# 2014_CanSat_main.net
KiCad netlist of a schematic drawn in EAGLE
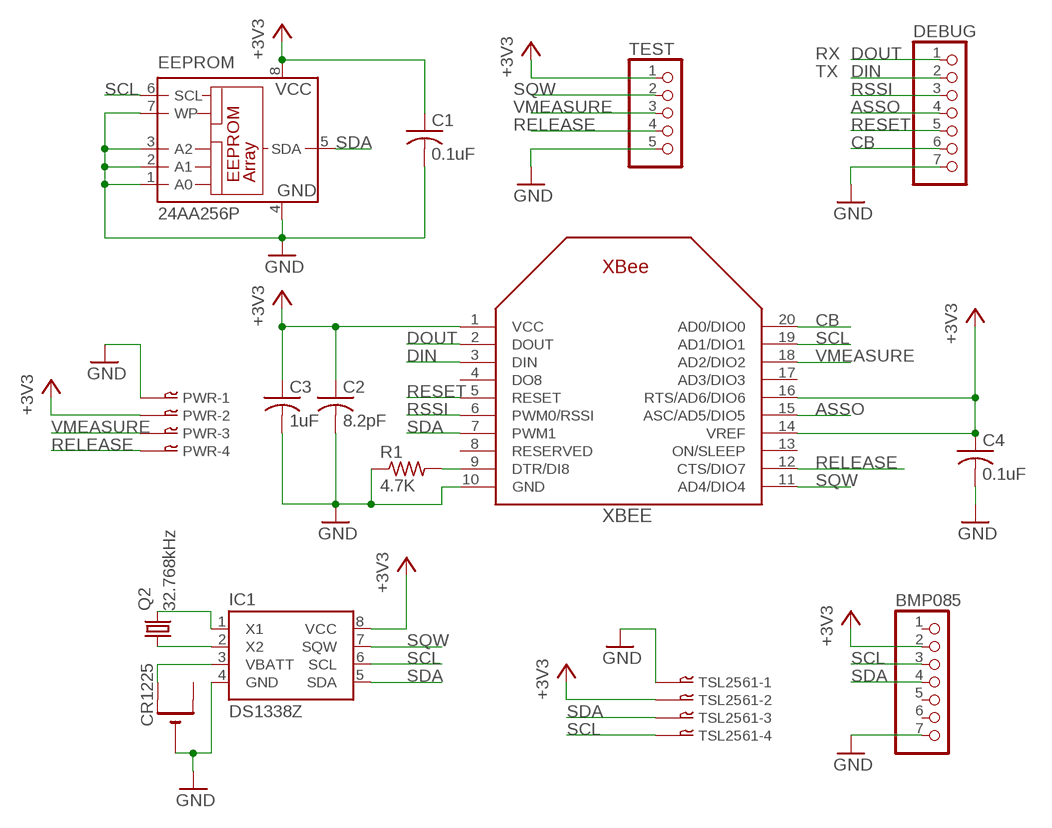
[diagram p0: schematic, sheet 1]

(export (version "E")
  (design (tool "Eeschema 10.0.6"))
  (components
    (comp (ref "BMP085")
      (value "PINHD-1X7")
      (footprint "eagle-import:1X07")
      (libsource (lib "eagle-import") (part "PINHD-1X7"))
    )
    (comp (ref "C1")
      (value "0.1uF")
      (footprint "eagle-import:C050-024X044")
      (libsource (lib "eagle-import") (part "C-US050-024X044"))
    )
    (comp (ref "C2")
      (value "8.2pF")
      (footprint "eagle-import:C050-024X044")
      (libsource (lib "eagle-import") (part "C-US050-024X044"))
    )
    (comp (ref "C3")
      (value "1uF")
      (footprint "eagle-import:C050-024X044")
      (libsource (lib "eagle-import") (part "C-US050-024X044"))
    )
    (comp (ref "C4")
      (value "0.1uF")
      (footprint "eagle-import:C050-024X044")
      (libsource (lib "eagle-import") (part "C-US050-024X044"))
    )
    (comp (ref "CR1225")
      (value "CR1220THM")
      (footprint "eagle-import:CR1220-THM")
      (libsource (lib "eagle-import") (part "CR1220THM"))
    )
    (comp (ref "DEBUG")
      (value "PINHD-1X7")
      (footprint "eagle-import:1X07")
      (libsource (lib "eagle-import") (part "PINHD-1X7"))
    )
    (comp (ref "EEPROM")
      (value "24AA256P")
      (footprint "eagle-import:DIL8")
      (fields (field (name "MF") "MICROCHIP") (field (name "MPN") "24AA256-I/P"))
      (libsource (lib "eagle-import") (part "24PAA256"))
    )
    (comp (ref "IC1")
      (value "DS1338Z")
      (footprint "eagle-import:SO08")
      (libsource (lib "eagle-import") (part "DS1338Z"))
    )
    (comp (ref "PWR")
      (value "04-JST-B4B-XH-A")
      (footprint "eagle-import:B4B-XH")
      (libsource (lib "eagle-import") (part "04-JST-B4B-XH-A"))
    )
    (comp (ref "Q2")
      (value "32.768kHz")
      (footprint "eagle-import:TC26H")
      (libsource (lib "eagle-import") (part "CRYSTALTC26H"))
    )
    (comp (ref "R1")
      (value "4.7K")
      (footprint "eagle-import:0309_10")
      (libsource (lib "eagle-import") (part "R-US_0309/10"))
    )
    (comp (ref "TEST")
      (value "PINHD-1X5")
      (footprint "eagle-import:1X05")
      (libsource (lib "eagle-import") (part "PINHD-1X5"))
    )
    (comp (ref "TSL2561")
      (value "04-JST-B4B-XH-A")
      (footprint "eagle-import:B4B-XH")
      (libsource (lib "eagle-import") (part "04-JST-B4B-XH-A"))
    )
    (comp (ref "XBEE")
      (value "XBEE")
      (footprint "eagle-import:XBEE")
      (libsource (lib "eagle-import") (part "XBEE"))
    )
  )
  (nets
    (net (code "1") (name "+3V3") (class "Default")
      (node (ref "BMP085") (pin "2") (pinfunction "2_2") (pintype "passive"))
      (node (ref "C1") (pin "1") (pinfunction "1_1") (pintype "passive"))
      (node (ref "C2") (pin "1") (pinfunction "1_1") (pintype "passive"))
      (node (ref "C3") (pin "1") (pinfunction "1_1") (pintype "passive"))
      (node (ref "C4") (pin "1") (pinfunction "1_1") (pintype "passive"))
      (node (ref "EEPROM") (pin "8") (pinfunction "VCC_8") (pintype "power_in"))
      (node (ref "IC1") (pin "8") (pinfunction "VCC_8") (pintype "bidirectional"))
      (node (ref "PWR") (pin "P$2") (pinfunction "1_P$2") (pintype "passive"))
      (node (ref "TEST") (pin "1") (pinfunction "1_1") (pintype "passive"))
      (node (ref "TSL2561") (pin "P$2") (pinfunction "1_P$2") (pintype "passive"))
      (node (ref "XBEE") (pin "1") (pinfunction "VCC_1") (pintype "power_in"))
      (node (ref "XBEE") (pin "14") (pinfunction "VREF_14") (pintype "input"))
      (node (ref "XBEE") (pin "16") (pinfunction "RTS/AD6/DIO6_16") (pintype "bidirectional"))
    )
    (net (code "2") (name "/ASSO") (class "Default")
      (node (ref "DEBUG") (pin "4") (pinfunction "4_4") (pintype "passive"))
      (node (ref "XBEE") (pin "15") (pinfunction "ASC/AD5/DIO5_15") (pintype "bidirectional"))
    )
    (net (code "3") (name "/CB") (class "Default")
      (node (ref "DEBUG") (pin "6") (pinfunction "6_6") (pintype "passive"))
      (node (ref "XBEE") (pin "20") (pinfunction "AD0/DIO0_20") (pintype "bidirectional"))
    )
    (net (code "4") (name "/DIN") (class "Default")
      (node (ref "DEBUG") (pin "2") (pinfunction "2_2") (pintype "passive"))
      (node (ref "XBEE") (pin "3") (pinfunction "DIN_3") (pintype "input"))
    )
    (net (code "5") (name "/DOUT") (class "Default")
      (node (ref "DEBUG") (pin "1") (pinfunction "1_1") (pintype "passive"))
      (node (ref "XBEE") (pin "2") (pinfunction "DOUT_2") (pintype "output"))
    )
    (net (code "6") (name "/RELEASE") (class "Default")
      (node (ref "PWR") (pin "P$4") (pinfunction "1_P$4") (pintype "passive"))
      (node (ref "TEST") (pin "4") (pinfunction "4_4") (pintype "passive"))
      (node (ref "XBEE") (pin "12") (pinfunction "CTS/DIO7_12") (pintype "bidirectional"))
    )
    (net (code "7") (name "/RESET") (class "Default")
      (node (ref "DEBUG") (pin "5") (pinfunction "5_5") (pintype "passive"))
      (node (ref "XBEE") (pin "5") (pinfunction "RESET_5") (pintype "input"))
    )
    (net (code "8") (name "/RSSI") (class "Default")
      (node (ref "DEBUG") (pin "3") (pinfunction "3_3") (pintype "passive"))
      (node (ref "XBEE") (pin "6") (pinfunction "PWM0/RSSI_6") (pintype "output"))
    )
    (net (code "9") (name "/SCL") (class "Default")
      (node (ref "BMP085") (pin "3") (pinfunction "3_3") (pintype "passive"))
      (node (ref "EEPROM") (pin "6") (pinfunction "SCL_6") (pintype "input"))
      (node (ref "IC1") (pin "6") (pinfunction "SCL_6") (pintype "bidirectional"))
      (node (ref "TSL2561") (pin "P$4") (pinfunction "1_P$4") (pintype "passive"))
      (node (ref "XBEE") (pin "19") (pinfunction "AD1/DIO1_19") (pintype "bidirectional"))
    )
    (net (code "10") (name "/SDA") (class "Default")
      (node (ref "BMP085") (pin "4") (pinfunction "4_4") (pintype "passive"))
      (node (ref "EEPROM") (pin "5") (pinfunction "SDA_5") (pintype "bidirectional"))
      (node (ref "IC1") (pin "5") (pinfunction "SDA_5") (pintype "bidirectional"))
      (node (ref "TSL2561") (pin "P$3") (pinfunction "1_P$3") (pintype "passive"))
      (node (ref "XBEE") (pin "7") (pinfunction "PWM1_7") (pintype "output"))
    )
    (net (code "11") (name "/SQW") (class "Default")
      (node (ref "IC1") (pin "7") (pinfunction "SQW_7") (pintype "bidirectional"))
      (node (ref "TEST") (pin "2") (pinfunction "2_2") (pintype "passive"))
      (node (ref "XBEE") (pin "11") (pinfunction "AD4/DIO4_11") (pintype "bidirectional"))
    )
    (net (code "12") (name "/VMEASURE") (class "Default")
      (node (ref "PWR") (pin "P$3") (pinfunction "1_P$3") (pintype "passive"))
      (node (ref "TEST") (pin "3") (pinfunction "3_3") (pintype "passive"))
      (node (ref "XBEE") (pin "18") (pinfunction "AD2/DIO2_18") (pintype "bidirectional"))
    )
    (net (code "13") (name "GND") (class "Default")
      (node (ref "BMP085") (pin "7") (pinfunction "7_7") (pintype "passive"))
      (node (ref "C1") (pin "2") (pinfunction "2_2") (pintype "passive"))
      (node (ref "C2") (pin "2") (pinfunction "2_2") (pintype "passive"))
      (node (ref "C3") (pin "2") (pinfunction "2_2") (pintype "passive"))
      (node (ref "C4") (pin "2") (pinfunction "2_2") (pintype "passive"))
      (node (ref "CR1225") (pin "-") (pinfunction "-_-") (pintype "passive"))
      (node (ref "DEBUG") (pin "7") (pinfunction "7_7") (pintype "passive"))
      (node (ref "EEPROM") (pin "1") (pinfunction "A0_1") (pintype "input"))
      (node (ref "EEPROM") (pin "2") (pinfunction "A1_2") (pintype "input"))
      (node (ref "EEPROM") (pin "3") (pinfunction "A2_3") (pintype "input"))
      (node (ref "EEPROM") (pin "4") (pinfunction "GND_4") (pintype "power_in"))
      (node (ref "EEPROM") (pin "7") (pinfunction "WP_7") (pintype "input"))
      (node (ref "IC1") (pin "4") (pinfunction "GND_4") (pintype "bidirectional"))
      (node (ref "PWR") (pin "P$1") (pinfunction "1_P$1") (pintype "passive"))
      (node (ref "R1") (pin "1") (pinfunction "1_1") (pintype "passive"))
      (node (ref "TEST") (pin "5") (pinfunction "5_5") (pintype "passive"))
      (node (ref "TSL2561") (pin "P$1") (pinfunction "1_P$1") (pintype "passive"))
      (node (ref "XBEE") (pin "10") (pinfunction "GND_10") (pintype "power_in"))
    )
    (net (code "14") (name "Net-(CR1225-+)") (class "Default")
      (node (ref "CR1225") (pin "+1") (pinfunction "+_+1") (pintype "passive"))
      (node (ref "IC1") (pin "3") (pinfunction "VBATT_3") (pintype "bidirectional"))
    )
    (net (code "15") (name "Net-(IC1-X1)") (class "Default")
      (node (ref "IC1") (pin "1") (pinfunction "X1_1") (pintype "bidirectional"))
      (node (ref "Q2") (pin "2") (pinfunction "2_2") (pintype "passive"))
    )
    (net (code "16") (name "Net-(IC1-X2)") (class "Default")
      (node (ref "IC1") (pin "2") (pinfunction "X2_2") (pintype "bidirectional"))
      (node (ref "Q2") (pin "1") (pinfunction "1_1") (pintype "passive"))
    )
    (net (code "17") (name "Net-(XBEE-DTR{slash}DI8)") (class "Default")
      (node (ref "R1") (pin "2") (pinfunction "2_2") (pintype "passive"))
      (node (ref "XBEE") (pin "9") (pinfunction "DTR/DI8_9") (pintype "input"))
    )
    (net (code "18") (name "unconnected-(BMP085-Pad1)") (class "Default")
      (node (ref "BMP085") (pin "1") (pinfunction "1_1") (pintype "passive"))
    )
    (net (code "19") (name "unconnected-(BMP085-Pad5)") (class "Default")
      (node (ref "BMP085") (pin "5") (pinfunction "5_5") (pintype "passive"))
    )
    (net (code "20") (name "unconnected-(BMP085-Pad6)") (class "Default")
      (node (ref "BMP085") (pin "6") (pinfunction "6_6") (pintype "passive"))
    )
    (net (code "21") (name "unconnected-(CR1225-+1-Pad+2)") (class "Default")
      (node (ref "CR1225") (pin "+2") (pinfunction "+1_+2") (pintype "passive"))
    )
    (net (code "22") (name "unconnected-(XBEE-AD3{slash}DIO3-Pad17)") (class "Default")
      (node (ref "XBEE") (pin "17") (pinfunction "AD3/DIO3_17") (pintype "bidirectional"))
    )
    (net (code "23") (name "unconnected-(XBEE-DO8-Pad4)") (class "Default")
      (node (ref "XBEE") (pin "4") (pinfunction "DO8_4") (pintype "output"))
    )
    (net (code "24") (name "unconnected-(XBEE-ON{slash}SLEEP-Pad13)") (class "Default")
      (node (ref "XBEE") (pin "13") (pinfunction "ON/SLEEP_13") (pintype "output"))
    )
    (net (code "25") (name "unconnected-(XBEE-RESERVED-Pad8)") (class "Default")
      (node (ref "XBEE") (pin "8") (pinfunction "RESERVED_8") (pintype "no_connect"))
    )
  )
)
